# DC-Motor-DRV.net
KiCad netlist of a schematic drawn in Altium Designer
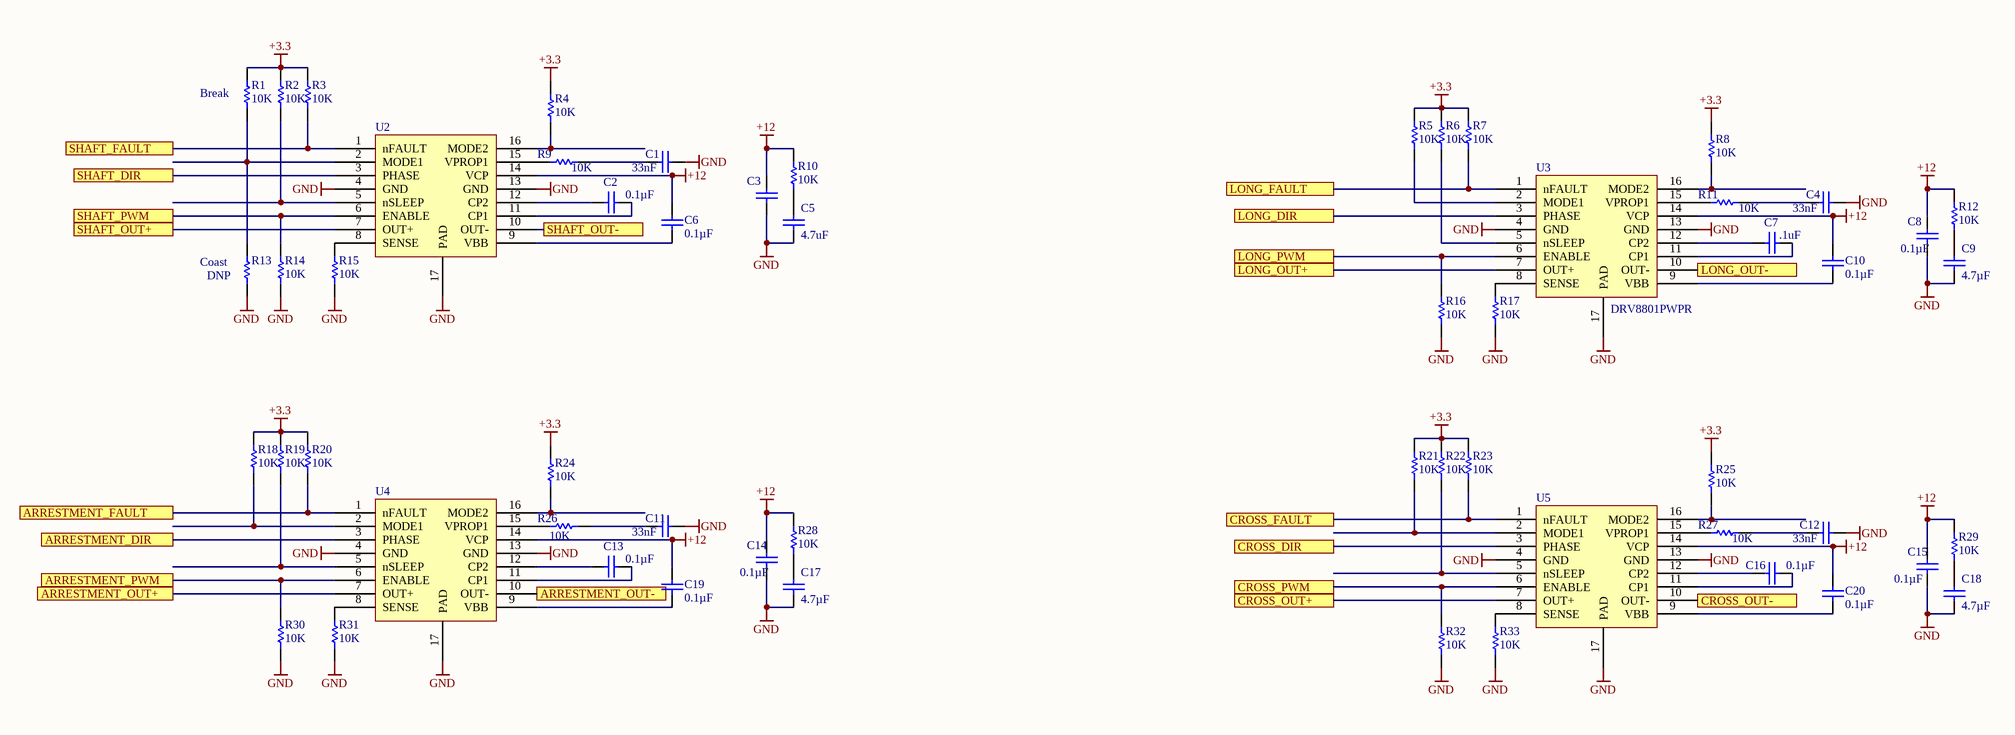
[diagram p0: DC-Motor-DRV.SchDoc]

(export (version "E")
  (design (tool "Eeschema 10.0.6"))
  (components
    (comp (ref "C1")
      (value "33nF")
      (footprint "CAPC0402(1005)60_L")
      (description "CAP CER 0.1UF 10V X7R 0402")
      (fields
        (field (name "MANUFACTURER") "Murata Electronics North America")
        (field (name "MANUFACTURER PART NUMBER") "GRM155R71A104KA01D")
      )
      (libsource (lib "Altium Content Vault") (part "CMP-1034-00252-1"))
    )
    (comp (ref "C2")
      (value "0.1uF")
      (footprint "CAPC0805(2012)145_N")
      (description "CAP CER 0.1UF 25V X7R 0805")
      (fields
        (field (name "MANUFACTURER") "Murata Electronics North America")
        (field (name "MANUFACTURER PART NUMBER") "GRM21BR71E104KA01L")
        (field (name "CAPACITANCE") "0.1µF")
      )
      (libsource (lib "Altium Content Vault") (part "CMP-1036-04795-1"))
    )
    (comp (ref "C3")
      (value "0.1uF")
      (footprint "CAPC0805(2012)145_N")
      (description "CAP CER 0.1UF 25V X7R 0805")
      (fields
        (field (name "MANUFACTURER") "Murata Electronics North America")
        (field (name "MANUFACTURER PART NUMBER") "GRM21BR71E104KA01L")
      )
      (libsource (lib "Altium Content Vault") (part "CMP-1036-04795-1"))
    )
    (comp (ref "C4")
      (value "33nF")
      (footprint "CAPC0402(1005)60_L")
      (description "CAP CER 33UF 10V X7R 0402")
      (fields
        (field (name "MANUFACTURER") "Murata Electronics North America")
        (field (name "MANUFACTURER PART NUMBER") "GRM155R71A104KA01D")
      )
      (libsource (lib "Altium Content Vault") (part "CMP-1034-00252-1"))
    )
    (comp (ref "C5")
      (value "4.7uF")
      (footprint "CAPC0805(2012)145_N")
      (description "CAP CER 4.7UF 25V 10% X7R 0805")
      (fields
        (field (name "MANUFACTURER") "Murata Electronics North America")
        (field (name "MANUFACTURER PART NUMBER") "GRM21BR71E104KA01L")
      )
      (libsource (lib "Altium Content Vault") (part "CMP-1036-04795-1"))
    )
    (comp (ref "C6")
      (value "0.1uF")
      (footprint "CAPC0805(2012)145_N")
      (description "CAP CER 0.1UF 25V X7R 0805")
      (fields
        (field (name "MANUFACTURER") "Murata Electronics North America")
        (field (name "MANUFACTURER PART NUMBER") "GRM21BR71E104KA01L")
        (field (name "CAPACITANCE") "0.1µF")
      )
      (libsource (lib "Altium Content Vault") (part "CMP-1036-04795-1"))
    )
    (comp (ref "C7")
      (value ".1uF")
      (footprint "CAPC0402(1005)60_M")
      (description "CAP 1nF 25V ±10% 0402 (1005 Metric) Thickness 0.6mm SMD")
      (fields (field (name "TOLERANCE") "Â±10%"))
      (libsource (lib "Altium Content Vault") (part "CMP-1034-01622-1"))
    )
    (comp (ref "C8")
      (value ".1uF")
      (footprint "CAPC0805(2012)145_N")
      (description "CAP CER 0.1UF 25V X7R 0805")
      (fields
        (field (name "MANUFACTURER") "Murata Electronics North America")
        (field (name "MANUFACTURER PART NUMBER") "GRM21BR71E104KA01L")
        (field (name "CAPACITANCE") "0.1µF")
      )
      (libsource (lib "Altium Content Vault") (part "CMP-1036-04795-1"))
    )
    (comp (ref "C9")
      (value "4.7uF")
      (footprint "CAPC0805(2012)145_N")
      (description "CAP CER 4.7UF 25V X7R 0805")
      (fields
        (field (name "MANUFACTURER") "Murata Electronics North America")
        (field (name "MANUFACTURER PART NUMBER") "GRM21BR71E104KA01L")
        (field (name "CAPACITANCE") "4.7µF")
      )
      (libsource (lib "Altium Content Vault") (part "CMP-1036-04795-1"))
    )
    (comp (ref "C10")
      (value ".1uF")
      (footprint "CAPC0805(2012)145_N")
      (description "CAP CER 0.1UF 25V X7R 0805")
      (fields
        (field (name "MANUFACTURER") "Murata Electronics North America")
        (field (name "MANUFACTURER PART NUMBER") "GRM21BR71E104KA01L")
        (field (name "CAPACITANCE") "0.1µF")
      )
      (libsource (lib "Altium Content Vault") (part "CMP-1036-04795-1"))
    )
    (comp (ref "C11")
      (value "33nF")
      (footprint "CAPC0402(1005)60_L")
      (description "CAP CER 0.1UF 10V X7R 0402")
      (fields
        (field (name "MANUFACTURER") "Murata Electronics North America")
        (field (name "MANUFACTURER PART NUMBER") "GRM155R71A104KA01D")
      )
      (libsource (lib "Altium Content Vault") (part "CMP-1034-00252-1"))
    )
    (comp (ref "C12")
      (value "33nF")
      (footprint "CAPC0402(1005)60_L")
      (description "CAP CER 3.3UF 10V X7R 0402")
      (fields
        (field (name "MANUFACTURER") "Murata Electronics North America")
        (field (name "MANUFACTURER PART NUMBER") "GRM155R71A104KA01D")
      )
      (libsource (lib "Altium Content Vault") (part "CMP-1034-00252-1"))
    )
    (comp (ref "C13")
      (value "CAP CER 0.1UF 25V X7R 0805")
      (footprint "CAPC0805(2012)145_N")
      (fields
        (field (name "MANUFACTURER") "Murata Electronics North America")
        (field (name "MANUFACTURER PART NUMBER") "GRM21BR71E104KA01L")
        (field (name "CAPACITANCE") "0.1µF")
        (field (name "TOLERANCE") "±10%")
      )
      (libsource (lib "Altium Content Vault") (part "CMP-1036-04795-1"))
    )
    (comp (ref "C14")
      (value "CAP CER 0.1UF 25V X7R 0805")
      (footprint "CAPC0805(2012)145_N")
      (fields
        (field (name "MANUFACTURER") "Murata Electronics North America")
        (field (name "MANUFACTURER PART NUMBER") "GRM21BR71E104KA01L")
        (field (name "CAPACITANCE") "0.1µF")
        (field (name "TOLERANCE") "±10%")
      )
      (libsource (lib "Altium Content Vault") (part "CMP-1036-04795-1"))
    )
    (comp (ref "C15")
      (value "0.1uF")
      (footprint "CAPC0805(2012)145_N")
      (description "CAP CER 0.1UF 25V X7R 0805")
      (fields
        (field (name "MANUFACTURER") "Murata Electronics North America")
        (field (name "MANUFACTURER PART NUMBER") "GRM21BR71E104KA01L")
        (field (name "CAPACITANCE") "0.1µF")
      )
      (libsource (lib "Altium Content Vault") (part "CMP-1036-04795-1"))
    )
    (comp (ref "C16")
      (value "0.1uF")
      (footprint "CAPC0805(2012)145_N")
      (description "CAP CER 0.1UF 25V X7R 0805")
      (fields
        (field (name "MANUFACTURER") "Murata Electronics North America")
        (field (name "MANUFACTURER PART NUMBER") "GRM21BR71E104KA01L")
        (field (name "CAPACITANCE") "0.1µF")
      )
      (libsource (lib "Altium Content Vault") (part "CMP-1036-04795-1"))
    )
    (comp (ref "C17")
      (value "CAP CER 0.1UF 25V X7R 0805")
      (footprint "CAPC0805(2012)145_N")
      (description "CAP CER 0.47UF 25V X7R 0805")
      (fields
        (field (name "MANUFACTURER") "Murata Electronics North America")
        (field (name "MANUFACTURER PART NUMBER") "GRM21BR71E104KA01L")
        (field (name "CAPACITANCE") "4.7µF")
      )
      (libsource (lib "Altium Content Vault") (part "CMP-1036-04795-1"))
    )
    (comp (ref "C18")
      (value "4.7uF")
      (footprint "CAPC0805(2012)145_N")
      (description "CAP CER 4.7UF 25V X7R 0805")
      (fields
        (field (name "MANUFACTURER") "Murata Electronics North America")
        (field (name "MANUFACTURER PART NUMBER") "GRM21BR71E104KA01L")
        (field (name "CAPACITANCE") "4.7µF")
      )
      (libsource (lib "Altium Content Vault") (part "CMP-1036-04795-1"))
    )
    (comp (ref "C19")
      (value "CAP CER 0.1UF 25V X7R 0805")
      (footprint "CAPC0805(2012)145_N")
      (fields
        (field (name "MANUFACTURER") "Murata Electronics North America")
        (field (name "MANUFACTURER PART NUMBER") "GRM21BR71E104KA01L")
        (field (name "CAPACITANCE") "0.1µF")
        (field (name "TOLERANCE") "±10%")
      )
      (libsource (lib "Altium Content Vault") (part "CMP-1036-04795-1"))
    )
    (comp (ref "C20")
      (value "0.1uF")
      (footprint "CAPC0805(2012)145_N")
      (description "CAP CER 0.1UF 25V X7R 0805")
      (fields
        (field (name "MANUFACTURER") "Murata Electronics North America")
        (field (name "MANUFACTURER PART NUMBER") "GRM21BR71E104KA01L")
        (field (name "CAPACITANCE") "0.1µF")
      )
      (libsource (lib "Altium Content Vault") (part "CMP-1036-04795-1"))
    )
    (comp (ref "R1")
      (value "10K")
      (footprint "RESC0805(2012)_L")
      (description "RES SMD 10K OHM 1% 1/8W 0805")
      (fields
        (field (name "MANUFACTURER") "Vishay Dale")
        (field (name "MANUFACTURER PART NUMBER") "CRCW080510K0FKEA")
      )
      (libsource (lib "Altium Content Vault") (part "CMP-1013-00215-1"))
    )
    (comp (ref "R2")
      (value "10K")
      (footprint "RESC0805(2012)_L")
      (description "RES SMD 10K OHM 1% 1/8W 0805")
      (fields
        (field (name "MANUFACTURER") "Vishay Dale")
        (field (name "MANUFACTURER PART NUMBER") "CRCW080510K0FKEA")
      )
      (libsource (lib "Altium Content Vault") (part "CMP-1013-00215-1"))
    )
    (comp (ref "R3")
      (value "10K")
      (footprint "RESC0805(2012)_L")
      (description "RES SMD 10K OHM 1% 1/8W 0805")
      (fields
        (field (name "MANUFACTURER") "Vishay Dale")
        (field (name "MANUFACTURER PART NUMBER") "CRCW080510K0FKEA")
      )
      (libsource (lib "Altium Content Vault") (part "CMP-1013-00215-1"))
    )
    (comp (ref "R4")
      (value "10K")
      (footprint "RESC0805(2012)_L")
      (description "RES SMD 10K OHM 1% 1/8W 0805")
      (fields
        (field (name "MANUFACTURER") "Vishay Dale")
        (field (name "MANUFACTURER PART NUMBER") "CRCW080510K0FKEA")
      )
      (libsource (lib "Altium Content Vault") (part "CMP-1013-00215-1"))
    )
    (comp (ref "R5")
      (value "10K")
      (footprint "RESC0805(2012)_L")
      (description "RES SMD 10K OHM 1% 1/8W 0805")
      (fields
        (field (name "MANUFACTURER") "Vishay Dale")
        (field (name "MANUFACTURER PART NUMBER") "CRCW080510K0FKEA")
      )
      (libsource (lib "Altium Content Vault") (part "CMP-1013-00215-1"))
    )
    (comp (ref "R6")
      (value "10K")
      (footprint "RESC0805(2012)_L")
      (description "RES SMD 10K OHM 1% 1/8W 0805")
      (fields
        (field (name "MANUFACTURER") "Vishay Dale")
        (field (name "MANUFACTURER PART NUMBER") "CRCW080510K0FKEA")
      )
      (libsource (lib "Altium Content Vault") (part "CMP-1013-00215-1"))
    )
    (comp (ref "R7")
      (value "10K")
      (footprint "RESC0805(2012)_L")
      (description "RES SMD 10K OHM 1% 1/8W 0805")
      (fields
        (field (name "MANUFACTURER") "Vishay Dale")
        (field (name "MANUFACTURER PART NUMBER") "CRCW080510K0FKEA")
      )
      (libsource (lib "Altium Content Vault") (part "CMP-1013-00215-1"))
    )
    (comp (ref "R8")
      (value "10K")
      (footprint "RESC0805(2012)_L")
      (description "RES SMD 10K OHM 1% 1/8W 0805")
      (fields
        (field (name "MANUFACTURER") "Vishay Dale")
        (field (name "MANUFACTURER PART NUMBER") "CRCW080510K0FKEA")
      )
      (libsource (lib "Altium Content Vault") (part "CMP-1013-00215-1"))
    )
    (comp (ref "R9")
      (value "10K")
      (footprint "RESC0805(2012)_L")
      (description "RES SMD 10K OHM 1% 1/8W 0805")
      (fields
        (field (name "MANUFACTURER") "Vishay Dale")
        (field (name "MANUFACTURER PART NUMBER") "CRCW080510K0FKEA")
      )
      (libsource (lib "Altium Content Vault") (part "CMP-1013-00215-1"))
    )
    (comp (ref "R10")
      (value "10K")
      (footprint "RESC0805(2012)_L")
      (description "RES SMD 1R OHM 1% 1/8W 0805")
      (fields
        (field (name "MANUFACTURER") "Vishay Dale")
        (field (name "MANUFACTURER PART NUMBER") "CRCW080510K0FKEA")
      )
      (libsource (lib "Altium Content Vault") (part "CMP-1013-00215-1"))
    )
    (comp (ref "R11")
      (value "10K")
      (footprint "RESC0805(2012)_L")
      (description "RES SMD 10K OHM 1% 1/8W 0805")
      (fields
        (field (name "MANUFACTURER") "Vishay Dale")
        (field (name "MANUFACTURER PART NUMBER") "CRCW080510K0FKEA")
      )
      (libsource (lib "Altium Content Vault") (part "CMP-1013-00215-1"))
    )
    (comp (ref "R12")
      (value "10K")
      (footprint "RESC0805(2012)_L")
      (description "RES SMD 1R OHM 1% 1/8W 0805")
      (fields
        (field (name "MANUFACTURER") "Vishay Dale")
        (field (name "MANUFACTURER PART NUMBER") "CRCW080510K0FKEA")
      )
      (libsource (lib "Altium Content Vault") (part "CMP-1013-00215-1"))
    )
    (comp (ref "R13")
      (value "DNP")
      (footprint "RESC0805(2012)_L")
      (description "RES SMD 10K OHM 1% 1/8W 0805")
      (fields
        (field (name "MANUFACTURER") "Vishay Dale")
        (field (name "MANUFACTURER PART NUMBER") "CRCW080510K0FKEA")
      )
      (libsource (lib "Altium Content Vault") (part "CMP-1013-00215-1"))
    )
    (comp (ref "R14")
      (value "10K")
      (footprint "RESC0805(2012)_L")
      (description "RES SMD 10K OHM 1% 1/8W 0805")
      (fields
        (field (name "MANUFACTURER") "Vishay Dale")
        (field (name "MANUFACTURER PART NUMBER") "CRCW080510K0FKEA")
      )
      (libsource (lib "Altium Content Vault") (part "CMP-1013-00215-1"))
    )
    (comp (ref "R15")
      (value "10K")
      (footprint "RESC0805(2012)_L")
      (description "RES SMD 10K OHM 1% 1/8W 0805")
      (fields
        (field (name "MANUFACTURER") "Vishay Dale")
        (field (name "MANUFACTURER PART NUMBER") "CRCW080510K0FKEA")
      )
      (libsource (lib "Altium Content Vault") (part "CMP-1013-00215-1"))
    )
    (comp (ref "R16")
      (value "10K")
      (footprint "RESC0805(2012)_L")
      (description "RES SMD 10K OHM 1% 1/8W 0805")
      (fields
        (field (name "MANUFACTURER") "Vishay Dale")
        (field (name "MANUFACTURER PART NUMBER") "CRCW080510K0FKEA")
      )
      (libsource (lib "Altium Content Vault") (part "CMP-1013-00215-1"))
    )
    (comp (ref "R17")
      (value "10K")
      (footprint "RESC0805(2012)_L")
      (description "RES SMD 10K OHM 1% 1/8W 0805")
      (fields
        (field (name "MANUFACTURER") "Vishay Dale")
        (field (name "MANUFACTURER PART NUMBER") "CRCW080510K0FKEA")
      )
      (libsource (lib "Altium Content Vault") (part "CMP-1013-00215-1"))
    )
    (comp (ref "R18")
      (value "10K")
      (footprint "RESC0805(2012)_L")
      (description "RES SMD 10K OHM 1% 1/8W 0805")
      (fields
        (field (name "MANUFACTURER") "Vishay Dale")
        (field (name "MANUFACTURER PART NUMBER") "CRCW080510K0FKEA")
      )
      (libsource (lib "Altium Content Vault") (part "CMP-1013-00215-1"))
    )
    (comp (ref "R19")
      (value "10K")
      (footprint "RESC0805(2012)_L")
      (description "RES SMD 10K OHM 1% 1/8W 0805")
      (fields
        (field (name "MANUFACTURER") "Vishay Dale")
        (field (name "MANUFACTURER PART NUMBER") "CRCW080510K0FKEA")
      )
      (libsource (lib "Altium Content Vault") (part "CMP-1013-00215-1"))
    )
    (comp (ref "R20")
      (value "10K")
      (footprint "RESC0805(2012)_L")
      (description "RES SMD 10K OHM 1% 1/8W 0805")
      (fields
        (field (name "MANUFACTURER") "Vishay Dale")
        (field (name "MANUFACTURER PART NUMBER") "CRCW080510K0FKEA")
      )
      (libsource (lib "Altium Content Vault") (part "CMP-1013-00215-1"))
    )
    (comp (ref "R21")
      (value "10K")
      (footprint "RESC0805(2012)_L")
      (description "RES SMD 10K OHM 1% 1/8W 0805")
      (fields
        (field (name "MANUFACTURER") "Vishay Dale")
        (field (name "MANUFACTURER PART NUMBER") "CRCW080510K0FKEA")
      )
      (libsource (lib "Altium Content Vault") (part "CMP-1013-00215-1"))
    )
    (comp (ref "R22")
      (value "10K")
      (footprint "RESC0805(2012)_L")
      (description "RES SMD 10K OHM 1% 1/8W 0805")
      (fields
        (field (name "MANUFACTURER") "Vishay Dale")
        (field (name "MANUFACTURER PART NUMBER") "CRCW080510K0FKEA")
      )
      (libsource (lib "Altium Content Vault") (part "CMP-1013-00215-1"))
    )
    (comp (ref "R23")
      (value "10K")
      (footprint "RESC0805(2012)_L")
      (description "RES SMD 10K OHM 1% 1/8W 0805")
      (fields
        (field (name "MANUFACTURER") "Vishay Dale")
        (field (name "MANUFACTURER PART NUMBER") "CRCW080510K0FKEA")
      )
      (libsource (lib "Altium Content Vault") (part "CMP-1013-00215-1"))
    )
    (comp (ref "R24")
      (value "10K")
      (footprint "RESC0805(2012)_L")
      (description "RES SMD 10K OHM 1% 1/8W 0805")
      (fields
        (field (name "MANUFACTURER") "Vishay Dale")
        (field (name "MANUFACTURER PART NUMBER") "CRCW080510K0FKEA")
      )
      (libsource (lib "Altium Content Vault") (part "CMP-1013-00215-1"))
    )
    (comp (ref "R25")
      (value "10K")
      (footprint "RESC0805(2012)_L")
      (description "RES SMD 10K OHM 1% 1/8W 0805")
      (fields
        (field (name "MANUFACTURER") "Vishay Dale")
        (field (name "MANUFACTURER PART NUMBER") "CRCW080510K0FKEA")
      )
      (libsource (lib "Altium Content Vault") (part "CMP-1013-00215-1"))
    )
    (comp (ref "R26")
      (value "10K")
      (footprint "RESC0805(2012)_L")
      (description "RES SMD 10K OHM 1% 1/8W 0805")
      (fields
        (field (name "MANUFACTURER") "Vishay Dale")
        (field (name "MANUFACTURER PART NUMBER") "CRCW080510K0FKEA")
      )
      (libsource (lib "Altium Content Vault") (part "CMP-1013-00215-1"))
    )
    (comp (ref "R27")
      (value "10K")
      (footprint "RESC0805(2012)_L")
      (description "RES SMD 10K OHM 1% 1/8W 0805")
      (fields
        (field (name "MANUFACTURER") "Vishay Dale")
        (field (name "MANUFACTURER PART NUMBER") "CRCW080510K0FKEA")
      )
      (libsource (lib "Altium Content Vault") (part "CMP-1013-00215-1"))
    )
    (comp (ref "R28")
      (value "10K")
      (footprint "RESC0805(2012)_L")
      (description "RES SMD 1R OHM 1% 1/8W 0805")
      (fields
        (field (name "MANUFACTURER") "Vishay Dale")
        (field (name "MANUFACTURER PART NUMBER") "CRCW080510K0FKEA")
      )
      (libsource (lib "Altium Content Vault") (part "CMP-1013-00215-1"))
    )
    (comp (ref "R29")
      (value "10K")
      (footprint "RESC0805(2012)_L")
      (description "RES SMD 1R OHM 1% 1/8W 0805")
      (fields
        (field (name "MANUFACTURER") "Vishay Dale")
        (field (name "MANUFACTURER PART NUMBER") "CRCW080510K0FKEA")
      )
      (libsource (lib "Altium Content Vault") (part "CMP-1013-00215-1"))
    )
    (comp (ref "R30")
      (value "10K")
      (footprint "RESC0805(2012)_L")
      (description "RES SMD 10K OHM 1% 1/8W 0805")
      (fields
        (field (name "MANUFACTURER") "Vishay Dale")
        (field (name "MANUFACTURER PART NUMBER") "CRCW080510K0FKEA")
      )
      (libsource (lib "Altium Content Vault") (part "CMP-1013-00215-1"))
    )
    (comp (ref "R31")
      (value "10K")
      (footprint "RESC0805(2012)_L")
      (description "RES SMD 10K OHM 1% 1/8W 0805")
      (fields
        (field (name "MANUFACTURER") "Vishay Dale")
        (field (name "MANUFACTURER PART NUMBER") "CRCW080510K0FKEA")
      )
      (libsource (lib "Altium Content Vault") (part "CMP-1013-00215-1"))
    )
    (comp (ref "R32")
      (value "10K")
      (footprint "RESC0805(2012)_L")
      (description "RES SMD 10K OHM 1% 1/8W 0805")
      (fields
        (field (name "MANUFACTURER") "Vishay Dale")
        (field (name "MANUFACTURER PART NUMBER") "CRCW080510K0FKEA")
      )
      (libsource (lib "Altium Content Vault") (part "CMP-1013-00215-1"))
    )
    (comp (ref "R33")
      (value "10K")
      (footprint "RESC0805(2012)_L")
      (description "RES SMD 10K OHM 1% 1/8W 0805")
      (fields
        (field (name "MANUFACTURER") "Vishay Dale")
        (field (name "MANUFACTURER PART NUMBER") "CRCW080510K0FKEA")
      )
      (libsource (lib "Altium Content Vault") (part "CMP-1013-00215-1"))
    )
    (comp (ref "U2")
      (value "DRV8801PWPR")
      (footprint "DRV8801PWPR")
      (description "IC MOTOR DRIVER PAR 16HTSSOP")
      (fields (field (name "MANUFACTURER") "Texas Instruments") (field (name "BASE PART NUMBER") "DRV8801"))
      (libsource (lib "ZLS_Schematic_lib") (part "DRV8801PWPR"))
    )
    (comp (ref "U3")
      (value "DRV8801PWPR")
      (footprint "DRV8801PWPR")
      (description "IC MOTOR DRIVER PAR 16HTSSOP")
      (fields (field (name "MANUFACTURER") "Texas Instruments") (field (name "BASE PART NUMBER") "DRV8801"))
      (libsource (lib "ZLS_Schematic_lib") (part "DRV8801PWPR"))
    )
    (comp (ref "U4")
      (value "DRV8801PWPR")
      (footprint "DRV8801PWPR")
      (description "IC MOTOR DRIVER PAR 16HTSSOP")
      (fields (field (name "MANUFACTURER") "Texas Instruments") (field (name "BASE PART NUMBER") "DRV8801"))
      (libsource (lib "ZLS_Schematic_lib") (part "DRV8801PWPR"))
    )
    (comp (ref "U5")
      (value "DRV8801PWPR")
      (footprint "DRV8801PWPR")
      (description "IC MOTOR DRIVER PAR 16HTSSOP")
      (fields (field (name "MANUFACTURER") "Texas Instruments") (field (name "BASE PART NUMBER") "DRV8801"))
      (libsource (lib "ZLS_Schematic_lib") (part "DRV8801PWPR"))
    )
  )
  (nets
    (net (code "1") (name "+3.3") (class "Default")
      (node (ref "R1") (pin "1") (pinfunction "1_1") (pintype "passive"))
      (node (ref "R18") (pin "1") (pinfunction "1_1") (pintype "passive"))
      (node (ref "R19") (pin "1") (pinfunction "1_1") (pintype "passive"))
      (node (ref "R2") (pin "1") (pinfunction "1_1") (pintype "passive"))
      (node (ref "R20") (pin "1") (pinfunction "1_1") (pintype "passive"))
      (node (ref "R21") (pin "1") (pinfunction "1_1") (pintype "passive"))
      (node (ref "R22") (pin "1") (pinfunction "1_1") (pintype "passive"))
      (node (ref "R23") (pin "1") (pinfunction "1_1") (pintype "passive"))
      (node (ref "R24") (pin "1") (pinfunction "1_1") (pintype "passive"))
      (node (ref "R25") (pin "1") (pinfunction "1_1") (pintype "passive"))
      (node (ref "R3") (pin "1") (pinfunction "1_1") (pintype "passive"))
      (node (ref "R4") (pin "1") (pinfunction "1_1") (pintype "passive"))
      (node (ref "R5") (pin "1") (pinfunction "1_1") (pintype "passive"))
      (node (ref "R6") (pin "1") (pinfunction "1_1") (pintype "passive"))
      (node (ref "R7") (pin "1") (pinfunction "1_1") (pintype "passive"))
      (node (ref "R8") (pin "1") (pinfunction "1_1") (pintype "passive"))
    )
    (net (code "2") (name "+12") (class "Default")
      (node (ref "C10") (pin "2") (pinfunction "2_2") (pintype "passive"))
      (node (ref "C14") (pin "1") (pinfunction "1_1") (pintype "passive"))
      (node (ref "C15") (pin "1") (pinfunction "1_1") (pintype "passive"))
      (node (ref "C19") (pin "2") (pinfunction "2_2") (pintype "passive"))
      (node (ref "C20") (pin "2") (pinfunction "2_2") (pintype "passive"))
      (node (ref "C3") (pin "1") (pinfunction "1_1") (pintype "passive"))
      (node (ref "C6") (pin "2") (pinfunction "2_2") (pintype "passive"))
      (node (ref "C8") (pin "1") (pinfunction "1_1") (pintype "passive"))
      (node (ref "R10") (pin "1") (pinfunction "1_1") (pintype "passive"))
      (node (ref "R12") (pin "1") (pinfunction "1_1") (pintype "passive"))
      (node (ref "R28") (pin "1") (pinfunction "1_1") (pintype "passive"))
      (node (ref "R29") (pin "1") (pinfunction "1_1") (pintype "passive"))
      (node (ref "U2") (pin "14") (pinfunction "VCP_14") (pintype "passive"))
      (node (ref "U3") (pin "14") (pinfunction "VCP_14") (pintype "passive"))
      (node (ref "U4") (pin "14") (pinfunction "VCP_14") (pintype "passive"))
      (node (ref "U5") (pin "14") (pinfunction "VCP_14") (pintype "passive"))
    )
    (net (code "3") (name "/ARRESTMENT_DIR") (class "Default")
      (node (ref "U4") (pin "3") (pinfunction "PHASE_3") (pintype "passive"))
    )
    (net (code "4") (name "/ARRESTMENT_FAULT") (class "Default")
      (node (ref "R20") (pin "2") (pinfunction "2_2") (pintype "passive"))
      (node (ref "U4") (pin "1") (pinfunction "nFAULT_1") (pintype "passive"))
    )
    (net (code "5") (name "/ARRESTMENT_OUT+") (class "Default")
      (node (ref "U4") (pin "7") (pinfunction "OUT+_7") (pintype "passive"))
    )
    (net (code "6") (name "/ARRESTMENT_OUT-") (class "Default")
      (node (ref "U4") (pin "10") (pinfunction "OUT-_10") (pintype "passive"))
    )
    (net (code "7") (name "/ARRESTMENT_PWM") (class "Default")
      (node (ref "R30") (pin "1") (pinfunction "1_1") (pintype "passive"))
      (node (ref "U4") (pin "6") (pinfunction "ENABLE_6") (pintype "passive"))
    )
    (net (code "8") (name "/CROSS_DIR") (class "Default")
      (node (ref "U5") (pin "3") (pinfunction "PHASE_3") (pintype "passive"))
    )
    (net (code "9") (name "/CROSS_FAULT") (class "Default")
      (node (ref "R23") (pin "2") (pinfunction "2_2") (pintype "passive"))
      (node (ref "U5") (pin "1") (pinfunction "nFAULT_1") (pintype "passive"))
    )
    (net (code "10") (name "/CROSS_OUT+") (class "Default")
      (node (ref "U5") (pin "7") (pinfunction "OUT+_7") (pintype "passive"))
    )
    (net (code "11") (name "/CROSS_OUT-") (class "Default")
      (node (ref "U5") (pin "10") (pinfunction "OUT-_10") (pintype "passive"))
    )
    (net (code "12") (name "/CROSS_PWM") (class "Default")
      (node (ref "R32") (pin "1") (pinfunction "1_1") (pintype "passive"))
      (node (ref "U5") (pin "6") (pinfunction "ENABLE_6") (pintype "passive"))
    )
    (net (code "13") (name "/LONG_DIR") (class "Default")
      (node (ref "U3") (pin "3") (pinfunction "PHASE_3") (pintype "passive"))
    )
    (net (code "14") (name "/LONG_FAULT") (class "Default")
      (node (ref "R7") (pin "2") (pinfunction "2_2") (pintype "passive"))
      (node (ref "U3") (pin "1") (pinfunction "nFAULT_1") (pintype "passive"))
    )
    (net (code "15") (name "/LONG_OUT+") (class "Default")
      (node (ref "U3") (pin "7") (pinfunction "OUT+_7") (pintype "passive"))
    )
    (net (code "16") (name "/LONG_OUT-") (class "Default")
      (node (ref "U3") (pin "10") (pinfunction "OUT-_10") (pintype "passive"))
    )
    (net (code "17") (name "/LONG_PWM") (class "Default")
      (node (ref "R16") (pin "1") (pinfunction "1_1") (pintype "passive"))
      (node (ref "U3") (pin "6") (pinfunction "ENABLE_6") (pintype "passive"))
    )
    (net (code "18") (name "/SHAFT_DIR") (class "Default")
      (node (ref "U2") (pin "3") (pinfunction "PHASE_3") (pintype "passive"))
    )
    (net (code "19") (name "/SHAFT_FAULT") (class "Default")
      (node (ref "R3") (pin "2") (pinfunction "2_2") (pintype "passive"))
      (node (ref "U2") (pin "1") (pinfunction "nFAULT_1") (pintype "passive"))
    )
    (net (code "20") (name "/SHAFT_OUT+") (class "Default")
      (node (ref "U2") (pin "7") (pinfunction "OUT+_7") (pintype "passive"))
    )
    (net (code "21") (name "/SHAFT_OUT-") (class "Default")
      (node (ref "U2") (pin "10") (pinfunction "OUT-_10") (pintype "passive"))
    )
    (net (code "22") (name "/SHAFT_PWM") (class "Default")
      (node (ref "R14") (pin "1") (pinfunction "1_1") (pintype "passive"))
      (node (ref "U2") (pin "6") (pinfunction "ENABLE_6") (pintype "passive"))
    )
    (net (code "23") (name "GND") (class "Default")
      (node (ref "C1") (pin "2") (pinfunction "2_2") (pintype "passive"))
      (node (ref "C11") (pin "2") (pinfunction "2_2") (pintype "passive"))
      (node (ref "C12") (pin "2") (pinfunction "2_2") (pintype "passive"))
      (node (ref "C14") (pin "2") (pinfunction "2_2") (pintype "passive"))
      (node (ref "C15") (pin "2") (pinfunction "2_2") (pintype "passive"))
      (node (ref "C17") (pin "2") (pinfunction "2_2") (pintype "passive"))
      (node (ref "C18") (pin "2") (pinfunction "2_2") (pintype "passive"))
      (node (ref "C3") (pin "2") (pinfunction "2_2") (pintype "passive"))
      (node (ref "C4") (pin "2") (pinfunction "2_2") (pintype "passive"))
      (node (ref "C5") (pin "2") (pinfunction "2_2") (pintype "passive"))
      (node (ref "C8") (pin "2") (pinfunction "2_2") (pintype "passive"))
      (node (ref "C9") (pin "2") (pinfunction "2_2") (pintype "passive"))
      (node (ref "R13") (pin "2") (pinfunction "2_2") (pintype "passive"))
      (node (ref "R14") (pin "2") (pinfunction "2_2") (pintype "passive"))
      (node (ref "R15") (pin "2") (pinfunction "2_2") (pintype "passive"))
      (node (ref "R16") (pin "2") (pinfunction "2_2") (pintype "passive"))
      (node (ref "R17") (pin "2") (pinfunction "2_2") (pintype "passive"))
      (node (ref "R30") (pin "2") (pinfunction "2_2") (pintype "passive"))
      (node (ref "R31") (pin "2") (pinfunction "2_2") (pintype "passive"))
      (node (ref "R32") (pin "2") (pinfunction "2_2") (pintype "passive"))
      (node (ref "R33") (pin "2") (pinfunction "2_2") (pintype "passive"))
      (node (ref "U2") (pin "13") (pinfunction "GND_13") (pintype "passive"))
      (node (ref "U2") (pin "17") (pinfunction "PAD_17") (pintype "passive"))
      (node (ref "U2") (pin "4") (pinfunction "GND_4") (pintype "passive"))
      (node (ref "U3") (pin "13") (pinfunction "GND_13") (pintype "passive"))
      (node (ref "U3") (pin "17") (pinfunction "PAD_17") (pintype "passive"))
      (node (ref "U3") (pin "4") (pinfunction "GND_4") (pintype "passive"))
      (node (ref "U4") (pin "13") (pinfunction "GND_13") (pintype "passive"))
      (node (ref "U4") (pin "17") (pinfunction "PAD_17") (pintype "passive"))
      (node (ref "U4") (pin "4") (pinfunction "GND_4") (pintype "passive"))
      (node (ref "U5") (pin "13") (pinfunction "GND_13") (pintype "passive"))
      (node (ref "U5") (pin "17") (pinfunction "PAD_17") (pintype "passive"))
      (node (ref "U5") (pin "4") (pinfunction "GND_4") (pintype "passive"))
    )
    (net (code "24") (name "Net-(C1-Pad1)") (class "Default")
      (node (ref "C1") (pin "1") (pinfunction "1_1") (pintype "passive"))
      (node (ref "R9") (pin "1") (pinfunction "1_1") (pintype "passive"))
    )
    (net (code "25") (name "Net-(C4-Pad1)") (class "Default")
      (node (ref "C4") (pin "1") (pinfunction "1_1") (pintype "passive"))
      (node (ref "R11") (pin "1") (pinfunction "1_1") (pintype "passive"))
    )
    (net (code "26") (name "Net-(C5-Pad1)") (class "Default")
      (node (ref "C5") (pin "1") (pinfunction "1_1") (pintype "passive"))
      (node (ref "R10") (pin "2") (pinfunction "2_2") (pintype "passive"))
    )
    (net (code "27") (name "Net-(C9-Pad1)") (class "Default")
      (node (ref "C9") (pin "1") (pinfunction "1_1") (pintype "passive"))
      (node (ref "R12") (pin "2") (pinfunction "2_2") (pintype "passive"))
    )
    (net (code "28") (name "Net-(C11-Pad1)") (class "Default")
      (node (ref "C11") (pin "1") (pinfunction "1_1") (pintype "passive"))
      (node (ref "R26") (pin "1") (pinfunction "1_1") (pintype "passive"))
    )
    (net (code "29") (name "Net-(C12-Pad1)") (class "Default")
      (node (ref "C12") (pin "1") (pinfunction "1_1") (pintype "passive"))
      (node (ref "R27") (pin "1") (pinfunction "1_1") (pintype "passive"))
    )
    (net (code "30") (name "Net-(C17-Pad1)") (class "Default")
      (node (ref "C17") (pin "1") (pinfunction "1_1") (pintype "passive"))
      (node (ref "R28") (pin "2") (pinfunction "2_2") (pintype "passive"))
    )
    (net (code "31") (name "Net-(C18-Pad1)") (class "Default")
      (node (ref "C18") (pin "1") (pinfunction "1_1") (pintype "passive"))
      (node (ref "R29") (pin "2") (pinfunction "2_2") (pintype "passive"))
    )
    (net (code "32") (name "Net-(U2-CP1)") (class "Default")
      (node (ref "C2") (pin "2") (pinfunction "2_2") (pintype "passive"))
      (node (ref "U2") (pin "11") (pinfunction "CP1_11") (pintype "passive"))
    )
    (net (code "33") (name "Net-(U2-CP2)") (class "Default")
      (node (ref "C2") (pin "1") (pinfunction "1_1") (pintype "passive"))
      (node (ref "U2") (pin "12") (pinfunction "CP2_12") (pintype "passive"))
    )
    (net (code "34") (name "Net-(U2-MODE1)") (class "Default")
      (node (ref "R1") (pin "2") (pinfunction "2_2") (pintype "passive"))
      (node (ref "R13") (pin "1") (pinfunction "1_1") (pintype "passive"))
      (node (ref "U2") (pin "2") (pinfunction "MODE1_2") (pintype "passive"))
    )
    (net (code "35") (name "Net-(U2-MODE2)") (class "Default")
      (node (ref "R4") (pin "2") (pinfunction "2_2") (pintype "passive"))
      (node (ref "U2") (pin "16") (pinfunction "MODE2_16") (pintype "passive"))
    )
    (net (code "36") (name "Net-(U2-SENSE)") (class "Default")
      (node (ref "R15") (pin "1") (pinfunction "1_1") (pintype "passive"))
      (node (ref "U2") (pin "8") (pinfunction "SENSE_8") (pintype "passive"))
    )
    (net (code "37") (name "Net-(U2-VBB)") (class "Default")
      (node (ref "C6") (pin "1") (pinfunction "1_1") (pintype "passive"))
      (node (ref "U2") (pin "9") (pinfunction "VBB_9") (pintype "passive"))
    )
    (net (code "38") (name "Net-(U2-VPROP1)") (class "Default")
      (node (ref "R9") (pin "2") (pinfunction "2_2") (pintype "passive"))
      (node (ref "U2") (pin "15") (pinfunction "VPROP1_15") (pintype "passive"))
    )
    (net (code "39") (name "Net-(U2-nSLEEP)") (class "Default")
      (node (ref "R2") (pin "2") (pinfunction "2_2") (pintype "passive"))
      (node (ref "U2") (pin "5") (pinfunction "nSLEEP_5") (pintype "passive"))
    )
    (net (code "40") (name "Net-(U3-CP1)") (class "Default")
      (node (ref "C7") (pin "2") (pinfunction "2_2") (pintype "passive"))
      (node (ref "U3") (pin "11") (pinfunction "CP1_11") (pintype "passive"))
    )
    (net (code "41") (name "Net-(U3-CP2)") (class "Default")
      (node (ref "C7") (pin "1") (pinfunction "1_1") (pintype "passive"))
      (node (ref "U3") (pin "12") (pinfunction "CP2_12") (pintype "passive"))
    )
    (net (code "42") (name "Net-(U3-MODE1)") (class "Default")
      (node (ref "R5") (pin "2") (pinfunction "2_2") (pintype "passive"))
      (node (ref "U3") (pin "2") (pinfunction "MODE1_2") (pintype "passive"))
    )
    (net (code "43") (name "Net-(U3-MODE2)") (class "Default")
      (node (ref "R8") (pin "2") (pinfunction "2_2") (pintype "passive"))
      (node (ref "U3") (pin "16") (pinfunction "MODE2_16") (pintype "passive"))
    )
    (net (code "44") (name "Net-(U3-SENSE)") (class "Default")
      (node (ref "R17") (pin "1") (pinfunction "1_1") (pintype "passive"))
      (node (ref "U3") (pin "8") (pinfunction "SENSE_8") (pintype "passive"))
    )
    (net (code "45") (name "Net-(U3-VBB)") (class "Default")
      (node (ref "C10") (pin "1") (pinfunction "1_1") (pintype "passive"))
      (node (ref "U3") (pin "9") (pinfunction "VBB_9") (pintype "passive"))
    )
    (net (code "46") (name "Net-(U3-VPROP1)") (class "Default")
      (node (ref "R11") (pin "2") (pinfunction "2_2") (pintype "passive"))
      (node (ref "U3") (pin "15") (pinfunction "VPROP1_15") (pintype "passive"))
    )
    (net (code "47") (name "Net-(U3-nSLEEP)") (class "Default")
      (node (ref "R6") (pin "2") (pinfunction "2_2") (pintype "passive"))
      (node (ref "U3") (pin "5") (pinfunction "nSLEEP_5") (pintype "passive"))
    )
    (net (code "48") (name "Net-(U4-CP1)") (class "Default")
      (node (ref "C13") (pin "2") (pinfunction "2_2") (pintype "passive"))
      (node (ref "U4") (pin "11") (pinfunction "CP1_11") (pintype "passive"))
    )
    (net (code "49") (name "Net-(U4-CP2)") (class "Default")
      (node (ref "C13") (pin "1") (pinfunction "1_1") (pintype "passive"))
      (node (ref "U4") (pin "12") (pinfunction "CP2_12") (pintype "passive"))
    )
    (net (code "50") (name "Net-(U4-MODE1)") (class "Default")
      (node (ref "R18") (pin "2") (pinfunction "2_2") (pintype "passive"))
      (node (ref "U4") (pin "2") (pinfunction "MODE1_2") (pintype "passive"))
    )
    (net (code "51") (name "Net-(U4-MODE2)") (class "Default")
      (node (ref "R24") (pin "2") (pinfunction "2_2") (pintype "passive"))
      (node (ref "U4") (pin "16") (pinfunction "MODE2_16") (pintype "passive"))
    )
    (net (code "52") (name "Net-(U4-SENSE)") (class "Default")
      (node (ref "R31") (pin "1") (pinfunction "1_1") (pintype "passive"))
      (node (ref "U4") (pin "8") (pinfunction "SENSE_8") (pintype "passive"))
    )
    (net (code "53") (name "Net-(U4-VBB)") (class "Default")
      (node (ref "C19") (pin "1") (pinfunction "1_1") (pintype "passive"))
      (node (ref "U4") (pin "9") (pinfunction "VBB_9") (pintype "passive"))
    )
    (net (code "54") (name "Net-(U4-VPROP1)") (class "Default")
      (node (ref "R26") (pin "2") (pinfunction "2_2") (pintype "passive"))
      (node (ref "U4") (pin "15") (pinfunction "VPROP1_15") (pintype "passive"))
    )
    (net (code "55") (name "Net-(U4-nSLEEP)") (class "Default")
      (node (ref "R19") (pin "2") (pinfunction "2_2") (pintype "passive"))
      (node (ref "U4") (pin "5") (pinfunction "nSLEEP_5") (pintype "passive"))
    )
    (net (code "56") (name "Net-(U5-CP1)") (class "Default")
      (node (ref "C16") (pin "2") (pinfunction "2_2") (pintype "passive"))
      (node (ref "U5") (pin "11") (pinfunction "CP1_11") (pintype "passive"))
    )
    (net (code "57") (name "Net-(U5-CP2)") (class "Default")
      (node (ref "C16") (pin "1") (pinfunction "1_1") (pintype "passive"))
      (node (ref "U5") (pin "12") (pinfunction "CP2_12") (pintype "passive"))
    )
    (net (code "58") (name "Net-(U5-MODE1)") (class "Default")
      (node (ref "R21") (pin "2") (pinfunction "2_2") (pintype "passive"))
      (node (ref "U5") (pin "2") (pinfunction "MODE1_2") (pintype "passive"))
    )
    (net (code "59") (name "Net-(U5-MODE2)") (class "Default")
      (node (ref "R25") (pin "2") (pinfunction "2_2") (pintype "passive"))
      (node (ref "U5") (pin "16") (pinfunction "MODE2_16") (pintype "passive"))
    )
    (net (code "60") (name "Net-(U5-SENSE)") (class "Default")
      (node (ref "R33") (pin "1") (pinfunction "1_1") (pintype "passive"))
      (node (ref "U5") (pin "8") (pinfunction "SENSE_8") (pintype "passive"))
    )
    (net (code "61") (name "Net-(U5-VBB)") (class "Default")
      (node (ref "C20") (pin "1") (pinfunction "1_1") (pintype "passive"))
      (node (ref "U5") (pin "9") (pinfunction "VBB_9") (pintype "passive"))
    )
    (net (code "62") (name "Net-(U5-VPROP1)") (class "Default")
      (node (ref "R27") (pin "2") (pinfunction "2_2") (pintype "passive"))
      (node (ref "U5") (pin "15") (pinfunction "VPROP1_15") (pintype "passive"))
    )
    (net (code "63") (name "Net-(U5-nSLEEP)") (class "Default")
      (node (ref "R22") (pin "2") (pinfunction "2_2") (pintype "passive"))
      (node (ref "U5") (pin "5") (pinfunction "nSLEEP_5") (pintype "passive"))
    )
  )
)
